# Bleep_Drum_Eurorack.net
KiCad netlist of a schematic drawn in EAGLE
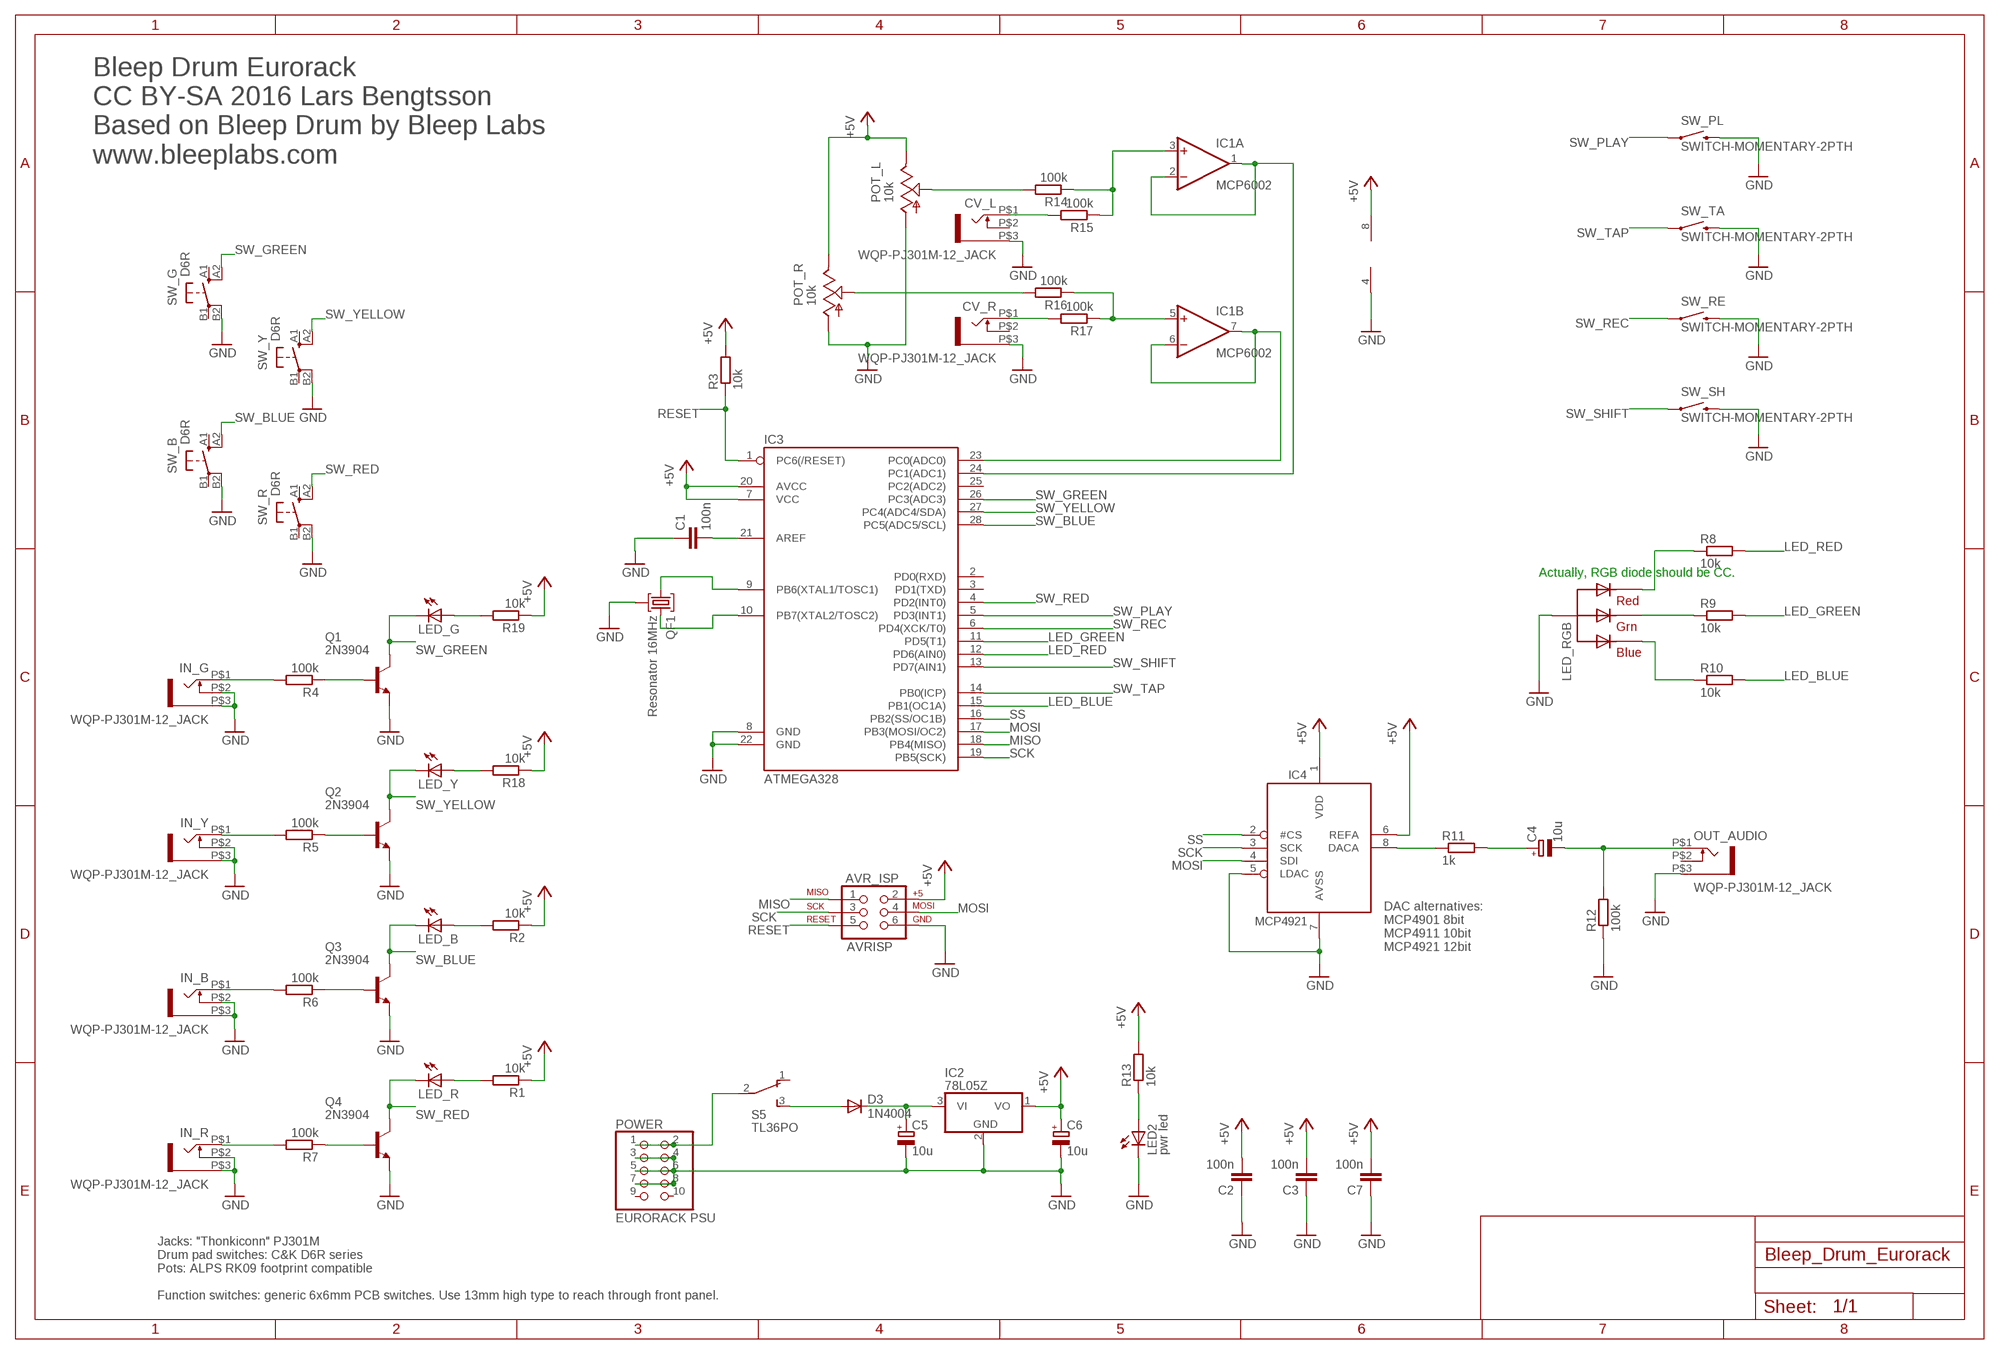
[diagram p0: schematic, sheet 1]

(export (version "E")
  (design (tool "Eeschema 10.0.6"))
  (components
    (comp (ref "AVR_ISP")
      (value "AVRISP")
      (footprint "eagle-import:2X3")
      (libsource (lib "eagle-import") (part "AVR_SPI_PRG_6PTH"))
    )
    (comp (ref "C1")
      (value "100n")
      (footprint "eagle-import:C025-025X050")
      (libsource (lib "eagle-import") (part "C-EU025-025X050"))
    )
    (comp (ref "C2")
      (value "100n")
      (footprint "eagle-import:C025-025X050")
      (libsource (lib "eagle-import") (part "C-EU025-025X050"))
    )
    (comp (ref "C3")
      (value "100n")
      (footprint "eagle-import:C025-025X050")
      (libsource (lib "eagle-import") (part "C-EU025-025X050"))
    )
    (comp (ref "C4")
      (value "10u")
      (footprint "eagle-import:E2,5-5")
      (libsource (lib "eagle-import") (part "CPOL-EUE2.5-5"))
    )
    (comp (ref "C5")
      (value "10u")
      (footprint "eagle-import:E2,5-5")
      (libsource (lib "eagle-import") (part "CPOL-EUE2.5-5"))
    )
    (comp (ref "C6")
      (value "10u")
      (footprint "eagle-import:E2,5-5")
      (libsource (lib "eagle-import") (part "CPOL-EUE2.5-5"))
    )
    (comp (ref "C7")
      (value "100n")
      (footprint "eagle-import:C025-025X050")
      (libsource (lib "eagle-import") (part "C-EU025-025X050"))
    )
    (comp (ref "CV_L")
      (value "WQP-PJ301M-12_JACK")
      (footprint "eagle-import:WQP-PJ301M-12_JACK")
      (libsource (lib "eagle-import") (part "WQP-PJ301M-12_JACK"))
    )
    (comp (ref "CV_R")
      (value "WQP-PJ301M-12_JACK")
      (footprint "eagle-import:WQP-PJ301M-12_JACK")
      (libsource (lib "eagle-import") (part "WQP-PJ301M-12_JACK"))
    )
    (comp (ref "D3")
      (value "1N4004")
      (footprint "eagle-import:D-2.5")
      (libsource (lib "eagle-import") (part "DIODE-D-2.5"))
    )
    (comp (ref "IC1")
      (value "MCP6002")
      (footprint "eagle-import:DIL08")
      (libsource (lib "eagle-import") (part "TL072P"))
    )
    (comp (ref "IC2")
      (value "78L05Z")
      (footprint "eagle-import:TO92")
      (libsource (lib "eagle-import") (part "78ZL05"))
    )
    (comp (ref "IC3")
      (value "ATMEGA328")
      (footprint "eagle-import:DIL28-3")
      (libsource (lib "eagle-import") (part "ATMEGA328P_PDIP"))
    )
    (comp (ref "IC4")
      (value "MCP4921")
      (footprint "eagle-import:DIL08")
      (libsource (lib "eagle-import") (part "MCP4921DIP8"))
    )
    (comp (ref "IN_B")
      (value "WQP-PJ301M-12_JACK")
      (footprint "eagle-import:WQP-PJ301M-12_JACK")
      (libsource (lib "eagle-import") (part "WQP-PJ301M-12_JACK"))
    )
    (comp (ref "IN_G")
      (value "WQP-PJ301M-12_JACK")
      (footprint "eagle-import:WQP-PJ301M-12_JACK")
      (libsource (lib "eagle-import") (part "WQP-PJ301M-12_JACK"))
    )
    (comp (ref "IN_R")
      (value "WQP-PJ301M-12_JACK")
      (footprint "eagle-import:WQP-PJ301M-12_JACK")
      (libsource (lib "eagle-import") (part "WQP-PJ301M-12_JACK"))
    )
    (comp (ref "IN_Y")
      (value "WQP-PJ301M-12_JACK")
      (footprint "eagle-import:WQP-PJ301M-12_JACK")
      (libsource (lib "eagle-import") (part "WQP-PJ301M-12_JACK"))
    )
    (comp (ref "LED2")
      (value "pwr led")
      (footprint "eagle-import:LED3MM")
      (libsource (lib "eagle-import") (part "LED3MM"))
    )
    (comp (ref "LED_B")
      (value "LED3MM")
      (footprint "eagle-import:LED3MM")
      (libsource (lib "eagle-import") (part "LED3MM"))
    )
    (comp (ref "LED_G")
      (value "LED3MM")
      (footprint "eagle-import:LED3MM")
      (libsource (lib "eagle-import") (part "LED3MM"))
    )
    (comp (ref "LED_R")
      (value "LED3MM")
      (footprint "eagle-import:LED3MM")
      (libsource (lib "eagle-import") (part "LED3MM"))
    )
    (comp (ref "LED_RGB")
      (value "RGBLED_CA-5MM")
      (footprint "eagle-import:LED5MMRGB")
      (libsource (lib "eagle-import") (part "RGBLED_CA-5MM"))
    )
    (comp (ref "LED_Y")
      (value "LED3MM")
      (footprint "eagle-import:LED3MM")
      (libsource (lib "eagle-import") (part "LED3MM"))
    )
    (comp (ref "OUT_AUDIO")
      (value "WQP-PJ301M-12_JACK")
      (footprint "eagle-import:WQP-PJ301M-12_JACK")
      (libsource (lib "eagle-import") (part "WQP-PJ301M-12_JACK"))
    )
    (comp (ref "POT_L")
      (value "10k")
      (footprint "eagle-import:ALPS_POT_VERTICAL")
      (libsource (lib "eagle-import") (part "POT_USVERTICAL"))
    )
    (comp (ref "POT_R")
      (value "10k")
      (footprint "eagle-import:ALPS_POT_VERTICAL")
      (libsource (lib "eagle-import") (part "POT_USVERTICAL"))
    )
    (comp (ref "POWER")
      (value "EURORACK PSU")
      (footprint "eagle-import:2X05")
      (libsource (lib "eagle-import") (part "PINHD-2X5"))
    )
    (comp (ref "Q1")
      (value "2N3904")
      (footprint "eagle-import:TO92")
      (libsource (lib "eagle-import") (part "2N3904"))
    )
    (comp (ref "Q2")
      (value "2N3904")
      (footprint "eagle-import:TO92")
      (libsource (lib "eagle-import") (part "2N3904"))
    )
    (comp (ref "Q3")
      (value "2N3904")
      (footprint "eagle-import:TO92")
      (libsource (lib "eagle-import") (part "2N3904"))
    )
    (comp (ref "Q4")
      (value "2N3904")
      (footprint "eagle-import:TO92")
      (libsource (lib "eagle-import") (part "2N3904"))
    )
    (comp (ref "QF1")
      (value "Resonator 16MHz")
      (footprint "eagle-import:UM1")
      (libsource (lib "eagle-import") (part "90M15AUM1"))
    )
    (comp (ref "R1")
      (value "10k")
      (footprint "eagle-import:0204V")
      (libsource (lib "eagle-import") (part "R-EU_0204/2V"))
    )
    (comp (ref "R2")
      (value "10k")
      (footprint "eagle-import:0204V")
      (libsource (lib "eagle-import") (part "R-EU_0204/2V"))
    )
    (comp (ref "R3")
      (value "10k")
      (footprint "eagle-import:0204V")
      (libsource (lib "eagle-import") (part "R-EU_0204/2V"))
    )
    (comp (ref "R4")
      (value "100k")
      (footprint "eagle-import:0204V")
      (libsource (lib "eagle-import") (part "R-EU_0204/2V"))
    )
    (comp (ref "R5")
      (value "100k")
      (footprint "eagle-import:0204V")
      (libsource (lib "eagle-import") (part "R-EU_0204/2V"))
    )
    (comp (ref "R6")
      (value "100k")
      (footprint "eagle-import:0204V")
      (libsource (lib "eagle-import") (part "R-EU_0204/2V"))
    )
    (comp (ref "R7")
      (value "100k")
      (footprint "eagle-import:0204V")
      (libsource (lib "eagle-import") (part "R-EU_0204/2V"))
    )
    (comp (ref "R8")
      (value "10k")
      (footprint "eagle-import:0204V")
      (libsource (lib "eagle-import") (part "R-EU_0204/2V"))
    )
    (comp (ref "R9")
      (value "10k")
      (footprint "eagle-import:0204V")
      (libsource (lib "eagle-import") (part "R-EU_0204/2V"))
    )
    (comp (ref "R10")
      (value "10k")
      (footprint "eagle-import:0204V")
      (libsource (lib "eagle-import") (part "R-EU_0204/2V"))
    )
    (comp (ref "R11")
      (value "1k")
      (footprint "eagle-import:0204V")
      (libsource (lib "eagle-import") (part "R-EU_0204/2V"))
    )
    (comp (ref "R12")
      (value "100k")
      (footprint "eagle-import:0204V")
      (libsource (lib "eagle-import") (part "R-EU_0204/2V"))
    )
    (comp (ref "R13")
      (value "10k")
      (footprint "eagle-import:0204V")
      (libsource (lib "eagle-import") (part "R-EU_0204/2V"))
    )
    (comp (ref "R14")
      (value "100k")
      (footprint "eagle-import:0204V")
      (libsource (lib "eagle-import") (part "R-EU_0204/2V"))
    )
    (comp (ref "R15")
      (value "100k")
      (footprint "eagle-import:0204V")
      (libsource (lib "eagle-import") (part "R-EU_0204/2V"))
    )
    (comp (ref "R16")
      (value "100k")
      (footprint "eagle-import:0204V")
      (libsource (lib "eagle-import") (part "R-EU_0204/2V"))
    )
    (comp (ref "R17")
      (value "100k")
      (footprint "eagle-import:0204V")
      (libsource (lib "eagle-import") (part "R-EU_0204/2V"))
    )
    (comp (ref "R18")
      (value "10k")
      (footprint "eagle-import:0204V")
      (libsource (lib "eagle-import") (part "R-EU_0204/2V"))
    )
    (comp (ref "R19")
      (value "10k")
      (footprint "eagle-import:0204V")
      (libsource (lib "eagle-import") (part "R-EU_0204/2V"))
    )
    (comp (ref "S5")
      (value "TL36PO")
      (footprint "eagle-import:TL3XPO")
      (libsource (lib "eagle-import") (part "TL36PO"))
    )
    (comp (ref "SW_B")
      (value "D6R")
      (footprint "eagle-import:D6R")
      (libsource (lib "eagle-import") (part "D6R"))
    )
    (comp (ref "SW_G")
      (value "D6R")
      (footprint "eagle-import:D6R")
      (libsource (lib "eagle-import") (part "D6R"))
    )
    (comp (ref "SW_PL")
      (value "SWITCH-MOMENTARY-2PTH")
      (footprint "eagle-import:TACTILE-PTH")
      (libsource (lib "eagle-import") (part "SWITCH-MOMENTARY-2PTH"))
    )
    (comp (ref "SW_R")
      (value "D6R")
      (footprint "eagle-import:D6R")
      (libsource (lib "eagle-import") (part "D6R"))
    )
    (comp (ref "SW_RE")
      (value "SWITCH-MOMENTARY-2PTH")
      (footprint "eagle-import:TACTILE-PTH")
      (libsource (lib "eagle-import") (part "SWITCH-MOMENTARY-2PTH"))
    )
    (comp (ref "SW_SH")
      (value "SWITCH-MOMENTARY-2PTH")
      (footprint "eagle-import:TACTILE-PTH")
      (libsource (lib "eagle-import") (part "SWITCH-MOMENTARY-2PTH"))
    )
    (comp (ref "SW_TA")
      (value "SWITCH-MOMENTARY-2PTH")
      (footprint "eagle-import:TACTILE-PTH")
      (libsource (lib "eagle-import") (part "SWITCH-MOMENTARY-2PTH"))
    )
    (comp (ref "SW_Y")
      (value "D6R")
      (footprint "eagle-import:D6R")
      (libsource (lib "eagle-import") (part "D6R"))
    )
  )
  (nets
    (net (code "1") (name "+5V") (class "Default")
      (node (ref "AVR_ISP") (pin "2") (pinfunction "2_2") (pintype "passive"))
      (node (ref "C2") (pin "2") (pinfunction "2_2") (pintype "passive"))
      (node (ref "C3") (pin "2") (pinfunction "2_2") (pintype "passive"))
      (node (ref "C6") (pin "+") (pinfunction "+_+") (pintype "passive"))
      (node (ref "C7") (pin "2") (pinfunction "2_2") (pintype "passive"))
      (node (ref "IC1") (pin "8") (pinfunction "V+_8") (pintype "power_in"))
      (node (ref "IC2") (pin "1") (pinfunction "VO_1") (pintype "passive"))
      (node (ref "IC3") (pin "20") (pinfunction "AVCC_20") (pintype "bidirectional"))
      (node (ref "IC3") (pin "7") (pinfunction "VCC_7") (pintype "bidirectional"))
      (node (ref "IC4") (pin "1") (pinfunction "VDD_1") (pintype "power_in"))
      (node (ref "IC4") (pin "6") (pinfunction "REFA_6") (pintype "input"))
      (node (ref "POT_L") (pin "P$1") (pinfunction "E_P$1") (pintype "passive"))
      (node (ref "POT_R") (pin "P$1") (pinfunction "E_P$1") (pintype "passive"))
      (node (ref "R1") (pin "1") (pinfunction "1_1") (pintype "passive"))
      (node (ref "R13") (pin "2") (pinfunction "2_2") (pintype "passive"))
      (node (ref "R18") (pin "1") (pinfunction "1_1") (pintype "passive"))
      (node (ref "R19") (pin "1") (pinfunction "1_1") (pintype "passive"))
      (node (ref "R2") (pin "1") (pinfunction "1_1") (pintype "passive"))
      (node (ref "R3") (pin "2") (pinfunction "2_2") (pintype "passive"))
    )
    (net (code "2") (name "/LED_BLUE") (class "Default")
      (node (ref "IC3") (pin "15") (pinfunction "PB1(OC1A)_15") (pintype "bidirectional"))
      (node (ref "R10") (pin "2") (pinfunction "2_2") (pintype "passive"))
    )
    (net (code "3") (name "/LED_GREEN") (class "Default")
      (node (ref "IC3") (pin "11") (pinfunction "PD5(T1)_11") (pintype "bidirectional"))
      (node (ref "R9") (pin "2") (pinfunction "2_2") (pintype "passive"))
    )
    (net (code "4") (name "/LED_RED") (class "Default")
      (node (ref "IC3") (pin "12") (pinfunction "PD6(AIN0)_12") (pintype "bidirectional"))
      (node (ref "R8") (pin "2") (pinfunction "2_2") (pintype "passive"))
    )
    (net (code "5") (name "/MISO") (class "Default")
      (node (ref "AVR_ISP") (pin "1") (pinfunction "1_1") (pintype "passive"))
      (node (ref "IC3") (pin "18") (pinfunction "PB4(MISO)_18") (pintype "bidirectional"))
    )
    (net (code "6") (name "/MOSI") (class "Default")
      (node (ref "AVR_ISP") (pin "4") (pinfunction "4_4") (pintype "passive"))
      (node (ref "IC3") (pin "17") (pinfunction "PB3(MOSI/OC2)_17") (pintype "bidirectional"))
      (node (ref "IC4") (pin "4") (pinfunction "SDI_4") (pintype "input"))
    )
    (net (code "7") (name "/RESET") (class "Default")
      (node (ref "AVR_ISP") (pin "5") (pinfunction "5_5") (pintype "passive"))
      (node (ref "IC3") (pin "1") (pinfunction "PC6(/RESET)_1") (pintype "bidirectional"))
      (node (ref "R3") (pin "1") (pinfunction "1_1") (pintype "passive"))
    )
    (net (code "8") (name "/SCK") (class "Default")
      (node (ref "AVR_ISP") (pin "3") (pinfunction "3_3") (pintype "passive"))
      (node (ref "IC3") (pin "19") (pinfunction "PB5(SCK)_19") (pintype "bidirectional"))
      (node (ref "IC4") (pin "3") (pinfunction "SCK_3") (pintype "input"))
    )
    (net (code "9") (name "/SS") (class "Default")
      (node (ref "IC3") (pin "16") (pinfunction "PB2(SS/OC1B)_16") (pintype "bidirectional"))
      (node (ref "IC4") (pin "2") (pinfunction "#CS_2") (pintype "input"))
    )
    (net (code "10") (name "/SW_BLUE") (class "Default")
      (node (ref "IC3") (pin "28") (pinfunction "PC5(ADC5/SCL)_28") (pintype "bidirectional"))
      (node (ref "LED_B") (pin "K") (pinfunction "C_K") (pintype "passive"))
      (node (ref "Q3") (pin "1") (pinfunction "C_1") (pintype "passive"))
      (node (ref "SW_B") (pin "A2") (pinfunction "S1_A2") (pintype "passive"))
    )
    (net (code "11") (name "/SW_GREEN") (class "Default")
      (node (ref "IC3") (pin "26") (pinfunction "PC3(ADC3)_26") (pintype "bidirectional"))
      (node (ref "LED_G") (pin "K") (pinfunction "C_K") (pintype "passive"))
      (node (ref "Q1") (pin "1") (pinfunction "C_1") (pintype "passive"))
      (node (ref "SW_G") (pin "A2") (pinfunction "S1_A2") (pintype "passive"))
    )
    (net (code "12") (name "/SW_PLAY") (class "Default")
      (node (ref "IC3") (pin "5") (pinfunction "PD3(INT1)_5") (pintype "bidirectional"))
      (node (ref "SW_PL") (pin "1") (pinfunction "1_1") (pintype "passive"))
    )
    (net (code "13") (name "/SW_REC") (class "Default")
      (node (ref "IC3") (pin "6") (pinfunction "PD4(XCK/T0)_6") (pintype "bidirectional"))
      (node (ref "SW_RE") (pin "1") (pinfunction "1_1") (pintype "passive"))
    )
    (net (code "14") (name "/SW_RED") (class "Default")
      (node (ref "IC3") (pin "4") (pinfunction "PD2(INT0)_4") (pintype "bidirectional"))
      (node (ref "LED_R") (pin "K") (pinfunction "C_K") (pintype "passive"))
      (node (ref "Q4") (pin "1") (pinfunction "C_1") (pintype "passive"))
      (node (ref "SW_R") (pin "A2") (pinfunction "S1_A2") (pintype "passive"))
    )
    (net (code "15") (name "/SW_SHIFT") (class "Default")
      (node (ref "IC3") (pin "13") (pinfunction "PD7(AIN1)_13") (pintype "bidirectional"))
      (node (ref "SW_SH") (pin "1") (pinfunction "1_1") (pintype "passive"))
    )
    (net (code "16") (name "/SW_TAP") (class "Default")
      (node (ref "IC3") (pin "14") (pinfunction "PB0(ICP)_14") (pintype "bidirectional"))
      (node (ref "SW_TA") (pin "1") (pinfunction "1_1") (pintype "passive"))
    )
    (net (code "17") (name "/SW_YELLOW") (class "Default")
      (node (ref "IC3") (pin "27") (pinfunction "PC4(ADC4/SDA)_27") (pintype "bidirectional"))
      (node (ref "LED_Y") (pin "K") (pinfunction "C_K") (pintype "passive"))
      (node (ref "Q2") (pin "1") (pinfunction "C_1") (pintype "passive"))
      (node (ref "SW_Y") (pin "A2") (pinfunction "S1_A2") (pintype "passive"))
    )
    (net (code "18") (name "GND") (class "Default")
      (node (ref "AVR_ISP") (pin "6") (pinfunction "6_6") (pintype "passive"))
      (node (ref "C1") (pin "1") (pinfunction "1_1") (pintype "passive"))
      (node (ref "C2") (pin "1") (pinfunction "1_1") (pintype "passive"))
      (node (ref "C3") (pin "1") (pinfunction "1_1") (pintype "passive"))
      (node (ref "C5") (pin "-") (pinfunction "-_-") (pintype "passive"))
      (node (ref "C6") (pin "-") (pinfunction "-_-") (pintype "passive"))
      (node (ref "C7") (pin "1") (pinfunction "1_1") (pintype "passive"))
      (node (ref "CV_L") (pin "P$3") (pinfunction "1_P$3") (pintype "passive"))
      (node (ref "CV_R") (pin "P$3") (pinfunction "1_P$3") (pintype "passive"))
      (node (ref "IC1") (pin "4") (pinfunction "V-_4") (pintype "power_in"))
      (node (ref "IC2") (pin "2") (pinfunction "GND_2") (pintype "passive"))
      (node (ref "IC3") (pin "22") (pinfunction "GND_22") (pintype "bidirectional"))
      (node (ref "IC3") (pin "8") (pinfunction "GND_8") (pintype "bidirectional"))
      (node (ref "IC4") (pin "5") (pinfunction "LDAC_5") (pintype "input"))
      (node (ref "IC4") (pin "7") (pinfunction "AVSS_7") (pintype "power_in"))
      (node (ref "IN_B") (pin "P$2") (pinfunction "3_P$2") (pintype "passive"))
      (node (ref "IN_B") (pin "P$3") (pinfunction "1_P$3") (pintype "passive"))
      (node (ref "IN_G") (pin "P$2") (pinfunction "3_P$2") (pintype "passive"))
      (node (ref "IN_G") (pin "P$3") (pinfunction "1_P$3") (pintype "passive"))
      (node (ref "IN_R") (pin "P$2") (pinfunction "3_P$2") (pintype "passive"))
      (node (ref "IN_R") (pin "P$3") (pinfunction "1_P$3") (pintype "passive"))
      (node (ref "IN_Y") (pin "P$2") (pinfunction "3_P$2") (pintype "passive"))
      (node (ref "IN_Y") (pin "P$3") (pinfunction "1_P$3") (pintype "passive"))
      (node (ref "LED2") (pin "K") (pinfunction "C_K") (pintype "passive"))
      (node (ref "LED_RGB") (pin "2") (pinfunction "VCC_2") (pintype "bidirectional"))
      (node (ref "OUT_AUDIO") (pin "P$3") (pinfunction "1_P$3") (pintype "passive"))
      (node (ref "POT_L") (pin "P$3") (pinfunction "A_P$3") (pintype "passive"))
      (node (ref "POT_R") (pin "P$3") (pinfunction "A_P$3") (pintype "passive"))
      (node (ref "POWER") (pin "3") (pinfunction "3_3") (pintype "passive"))
      (node (ref "POWER") (pin "4") (pinfunction "4_4") (pintype "passive"))
      (node (ref "POWER") (pin "5") (pinfunction "5_5") (pintype "passive"))
      (node (ref "POWER") (pin "6") (pinfunction "6_6") (pintype "passive"))
      (node (ref "POWER") (pin "7") (pinfunction "7_7") (pintype "passive"))
      (node (ref "POWER") (pin "8") (pinfunction "8_8") (pintype "passive"))
      (node (ref "Q1") (pin "3") (pinfunction "E_3") (pintype "passive"))
      (node (ref "Q2") (pin "3") (pinfunction "E_3") (pintype "passive"))
      (node (ref "Q3") (pin "3") (pinfunction "E_3") (pintype "passive"))
      (node (ref "Q4") (pin "3") (pinfunction "E_3") (pintype "passive"))
      (node (ref "QF1") (pin "2") (pinfunction "2_2") (pintype "passive"))
      (node (ref "R12") (pin "1") (pinfunction "1_1") (pintype "passive"))
      (node (ref "SW_B") (pin "B2") (pinfunction "P1_B2") (pintype "passive"))
      (node (ref "SW_G") (pin "B2") (pinfunction "P1_B2") (pintype "passive"))
      (node (ref "SW_PL") (pin "3") (pinfunction "2_3") (pintype "passive"))
      (node (ref "SW_R") (pin "B2") (pinfunction "P1_B2") (pintype "passive"))
      (node (ref "SW_RE") (pin "3") (pinfunction "2_3") (pintype "passive"))
      (node (ref "SW_SH") (pin "3") (pinfunction "2_3") (pintype "passive"))
      (node (ref "SW_TA") (pin "3") (pinfunction "2_3") (pintype "passive"))
      (node (ref "SW_Y") (pin "B2") (pinfunction "P1_B2") (pintype "passive"))
    )
    (net (code "19") (name "Net-(C4-Pad+)") (class "Default")
      (node (ref "C4") (pin "+") (pinfunction "+_+") (pintype "passive"))
      (node (ref "R11") (pin "2") (pinfunction "2_2") (pintype "passive"))
    )
    (net (code "20") (name "Net-(CV_L-2)") (class "Default")
      (node (ref "CV_L") (pin "P$1") (pinfunction "2_P$1") (pintype "passive"))
      (node (ref "R15") (pin "2") (pinfunction "2_2") (pintype "passive"))
    )
    (net (code "21") (name "Net-(CV_R-2)") (class "Default")
      (node (ref "CV_R") (pin "P$1") (pinfunction "2_P$1") (pintype "passive"))
      (node (ref "R17") (pin "2") (pinfunction "2_2") (pintype "passive"))
    )
    (net (code "22") (name "Net-(IC1A-+IN)") (class "Default")
      (node (ref "IC1") (pin "3") (pinfunction "+IN_3") (pintype "input"))
      (node (ref "R14") (pin "1") (pinfunction "1_1") (pintype "passive"))
      (node (ref "R15") (pin "1") (pinfunction "1_1") (pintype "passive"))
    )
    (net (code "23") (name "Net-(IC1A--IN)") (class "Default")
      (node (ref "IC1") (pin "1") (pinfunction "OUT_1") (pintype "output"))
      (node (ref "IC1") (pin "2") (pinfunction "-IN_2") (pintype "input"))
      (node (ref "IC3") (pin "24") (pinfunction "PC1(ADC1)_24") (pintype "bidirectional"))
    )
    (net (code "24") (name "Net-(IC1B-+IN)") (class "Default")
      (node (ref "IC1") (pin "5") (pinfunction "+IN_5") (pintype "input"))
      (node (ref "R16") (pin "1") (pinfunction "1_1") (pintype "passive"))
      (node (ref "R17") (pin "1") (pinfunction "1_1") (pintype "passive"))
    )
    (net (code "25") (name "Net-(IC1B--IN)") (class "Default")
      (node (ref "IC1") (pin "6") (pinfunction "-IN_6") (pintype "input"))
      (node (ref "IC1") (pin "7") (pinfunction "OUT_7") (pintype "output"))
      (node (ref "IC3") (pin "23") (pinfunction "PC0(ADC0)_23") (pintype "bidirectional"))
    )
    (net (code "26") (name "Net-(IC2-VI)") (class "Default")
      (node (ref "C5") (pin "+") (pinfunction "+_+") (pintype "passive"))
      (node (ref "D3") (pin "C") (pinfunction "C_C") (pintype "passive"))
      (node (ref "IC2") (pin "3") (pinfunction "VI_3") (pintype "input"))
    )
    (net (code "27") (name "Net-(IC3-AREF)") (class "Default")
      (node (ref "C1") (pin "2") (pinfunction "2_2") (pintype "passive"))
      (node (ref "IC3") (pin "21") (pinfunction "AREF_21") (pintype "bidirectional"))
    )
    (net (code "28") (name "Net-(IC3-PB6(XTAL1{slash}TOSC1))") (class "Default")
      (node (ref "IC3") (pin "9") (pinfunction "PB6(XTAL1/TOSC1)_9") (pintype "bidirectional"))
      (node (ref "QF1") (pin "1") (pinfunction "1_1") (pintype "passive"))
    )
    (net (code "29") (name "Net-(IC3-PB7(XTAL2{slash}TOSC2))") (class "Default")
      (node (ref "IC3") (pin "10") (pinfunction "PB7(XTAL2/TOSC2)_10") (pintype "bidirectional"))
      (node (ref "QF1") (pin "3") (pinfunction "3_3") (pintype "passive"))
    )
    (net (code "30") (name "Net-(IC4-DACA)") (class "Default")
      (node (ref "IC4") (pin "8") (pinfunction "DACA_8") (pintype "output"))
      (node (ref "R11") (pin "1") (pinfunction "1_1") (pintype "passive"))
    )
    (net (code "31") (name "Net-(IN_B-2)") (class "Default")
      (node (ref "IN_B") (pin "P$1") (pinfunction "2_P$1") (pintype "passive"))
      (node (ref "R6") (pin "2") (pinfunction "2_2") (pintype "passive"))
    )
    (net (code "32") (name "Net-(IN_G-2)") (class "Default")
      (node (ref "IN_G") (pin "P$1") (pinfunction "2_P$1") (pintype "passive"))
      (node (ref "R4") (pin "2") (pinfunction "2_2") (pintype "passive"))
    )
    (net (code "33") (name "Net-(IN_R-2)") (class "Default")
      (node (ref "IN_R") (pin "P$1") (pinfunction "2_P$1") (pintype "passive"))
      (node (ref "R7") (pin "2") (pinfunction "2_2") (pintype "passive"))
    )
    (net (code "34") (name "Net-(IN_Y-2)") (class "Default")
      (node (ref "IN_Y") (pin "P$1") (pinfunction "2_P$1") (pintype "passive"))
      (node (ref "R5") (pin "2") (pinfunction "2_2") (pintype "passive"))
    )
    (net (code "35") (name "Net-(LED2-PadA)") (class "Default")
      (node (ref "LED2") (pin "A") (pinfunction "A_A") (pintype "passive"))
      (node (ref "R13") (pin "1") (pinfunction "1_1") (pintype "passive"))
    )
    (net (code "36") (name "Net-(LED_B-PadA)") (class "Default")
      (node (ref "LED_B") (pin "A") (pinfunction "A_A") (pintype "passive"))
      (node (ref "R2") (pin "2") (pinfunction "2_2") (pintype "passive"))
    )
    (net (code "37") (name "Net-(LED_G-PadA)") (class "Default")
      (node (ref "LED_G") (pin "A") (pinfunction "A_A") (pintype "passive"))
      (node (ref "R19") (pin "2") (pinfunction "2_2") (pintype "passive"))
    )
    (net (code "38") (name "Net-(LED_R-PadA)") (class "Default")
      (node (ref "LED_R") (pin "A") (pinfunction "A_A") (pintype "passive"))
      (node (ref "R1") (pin "2") (pinfunction "2_2") (pintype "passive"))
    )
    (net (code "39") (name "Net-(LED_RGB-BLUE)") (class "Default")
      (node (ref "LED_RGB") (pin "4") (pinfunction "BLUE_4") (pintype "bidirectional"))
      (node (ref "R10") (pin "1") (pinfunction "1_1") (pintype "passive"))
    )
    (net (code "40") (name "Net-(LED_RGB-GREEN)") (class "Default")
      (node (ref "LED_RGB") (pin "3") (pinfunction "GREEN_3") (pintype "bidirectional"))
      (node (ref "R9") (pin "1") (pinfunction "1_1") (pintype "passive"))
    )
    (net (code "41") (name "Net-(LED_RGB-RED)") (class "Default")
      (node (ref "LED_RGB") (pin "1") (pinfunction "RED_1") (pintype "bidirectional"))
      (node (ref "R8") (pin "1") (pinfunction "1_1") (pintype "passive"))
    )
    (net (code "42") (name "Net-(LED_Y-PadA)") (class "Default")
      (node (ref "LED_Y") (pin "A") (pinfunction "A_A") (pintype "passive"))
      (node (ref "R18") (pin "2") (pinfunction "2_2") (pintype "passive"))
    )
    (net (code "43") (name "Net-(OUT_AUDIO-2)") (class "Default")
      (node (ref "C4") (pin "-") (pinfunction "-_-") (pintype "passive"))
      (node (ref "OUT_AUDIO") (pin "P$1") (pinfunction "2_P$1") (pintype "passive"))
      (node (ref "R12") (pin "2") (pinfunction "2_2") (pintype "passive"))
    )
    (net (code "44") (name "Net-(POT_L-S)") (class "Default")
      (node (ref "POT_L") (pin "P$2") (pinfunction "S_P$2") (pintype "passive"))
      (node (ref "R14") (pin "2") (pinfunction "2_2") (pintype "passive"))
    )
    (net (code "45") (name "Net-(POT_R-S)") (class "Default")
      (node (ref "POT_R") (pin "P$2") (pinfunction "S_P$2") (pintype "passive"))
      (node (ref "R16") (pin "2") (pinfunction "2_2") (pintype "passive"))
    )
    (net (code "46") (name "Net-(Q1-B)") (class "Default")
      (node (ref "Q1") (pin "2") (pinfunction "B_2") (pintype "passive"))
      (node (ref "R4") (pin "1") (pinfunction "1_1") (pintype "passive"))
    )
    (net (code "47") (name "Net-(Q2-B)") (class "Default")
      (node (ref "Q2") (pin "2") (pinfunction "B_2") (pintype "passive"))
      (node (ref "R5") (pin "1") (pinfunction "1_1") (pintype "passive"))
    )
    (net (code "48") (name "Net-(Q3-B)") (class "Default")
      (node (ref "Q3") (pin "2") (pinfunction "B_2") (pintype "passive"))
      (node (ref "R6") (pin "1") (pinfunction "1_1") (pintype "passive"))
    )
    (net (code "49") (name "Net-(Q4-B)") (class "Default")
      (node (ref "Q4") (pin "2") (pinfunction "B_2") (pintype "passive"))
      (node (ref "R7") (pin "1") (pinfunction "1_1") (pintype "passive"))
    )
    (net (code "50") (name "Net-(S5-P)") (class "Default")
      (node (ref "POWER") (pin "1") (pinfunction "1_1") (pintype "passive"))
      (node (ref "POWER") (pin "2") (pinfunction "2_2") (pintype "passive"))
      (node (ref "S5") (pin "2") (pinfunction "P_2") (pintype "passive"))
    )
    (net (code "51") (name "Net-(S5-S)") (class "Default")
      (node (ref "D3") (pin "A") (pinfunction "A_A") (pintype "passive"))
      (node (ref "S5") (pin "3") (pinfunction "S_3") (pintype "passive"))
    )
    (net (code "52") (name "unconnected-(CV_L-3-PadP$2)") (class "Default")
      (node (ref "CV_L") (pin "P$2") (pinfunction "3_P$2") (pintype "passive"))
    )
    (net (code "53") (name "unconnected-(CV_R-3-PadP$2)") (class "Default")
      (node (ref "CV_R") (pin "P$2") (pinfunction "3_P$2") (pintype "passive"))
    )
    (net (code "54") (name "unconnected-(IC3-PC2(ADC2)-Pad25)") (class "Default")
      (node (ref "IC3") (pin "25") (pinfunction "PC2(ADC2)_25") (pintype "bidirectional"))
    )
    (net (code "55") (name "unconnected-(IC3-PD0(RXD)-Pad2)") (class "Default")
      (node (ref "IC3") (pin "2") (pinfunction "PD0(RXD)_2") (pintype "bidirectional"))
    )
    (net (code "56") (name "unconnected-(IC3-PD1(TXD)-Pad3)") (class "Default")
      (node (ref "IC3") (pin "3") (pinfunction "PD1(TXD)_3") (pintype "bidirectional"))
    )
    (net (code "57") (name "unconnected-(OUT_AUDIO-3-PadP$2)") (class "Default")
      (node (ref "OUT_AUDIO") (pin "P$2") (pinfunction "3_P$2") (pintype "passive"))
    )
    (net (code "58") (name "unconnected-(POWER-Pad9)") (class "Default")
      (node (ref "POWER") (pin "9") (pinfunction "9_9") (pintype "passive"))
    )
    (net (code "59") (name "unconnected-(POWER-Pad10)") (class "Default")
      (node (ref "POWER") (pin "10") (pinfunction "10_10") (pintype "passive"))
    )
    (net (code "60") (name "unconnected-(S5-O-Pad1)") (class "Default")
      (node (ref "S5") (pin "1") (pinfunction "O_1") (pintype "passive"))
    )
    (net (code "61") (name "unconnected-(SW_B-P-PadB1)") (class "Default")
      (node (ref "SW_B") (pin "B1") (pinfunction "P_B1") (pintype "passive"))
    )
    (net (code "62") (name "unconnected-(SW_B-S-PadA1)") (class "Default")
      (node (ref "SW_B") (pin "A1") (pinfunction "S_A1") (pintype "passive"))
    )
    (net (code "63") (name "unconnected-(SW_G-P-PadB1)") (class "Default")
      (node (ref "SW_G") (pin "B1") (pinfunction "P_B1") (pintype "passive"))
    )
    (net (code "64") (name "unconnected-(SW_G-S-PadA1)") (class "Default")
      (node (ref "SW_G") (pin "A1") (pinfunction "S_A1") (pintype "passive"))
    )
    (net (code "65") (name "unconnected-(SW_R-P-PadB1)") (class "Default")
      (node (ref "SW_R") (pin "B1") (pinfunction "P_B1") (pintype "passive"))
    )
    (net (code "66") (name "unconnected-(SW_R-S-PadA1)") (class "Default")
      (node (ref "SW_R") (pin "A1") (pinfunction "S_A1") (pintype "passive"))
    )
    (net (code "67") (name "unconnected-(SW_Y-P-PadB1)") (class "Default")
      (node (ref "SW_Y") (pin "B1") (pinfunction "P_B1") (pintype "passive"))
    )
    (net (code "68") (name "unconnected-(SW_Y-S-PadA1)") (class "Default")
      (node (ref "SW_Y") (pin "A1") (pinfunction "S_A1") (pintype "passive"))
    )
  )
)
